# Boris_IO_5.net
KiCad netlist of a schematic drawn in Altium Designer
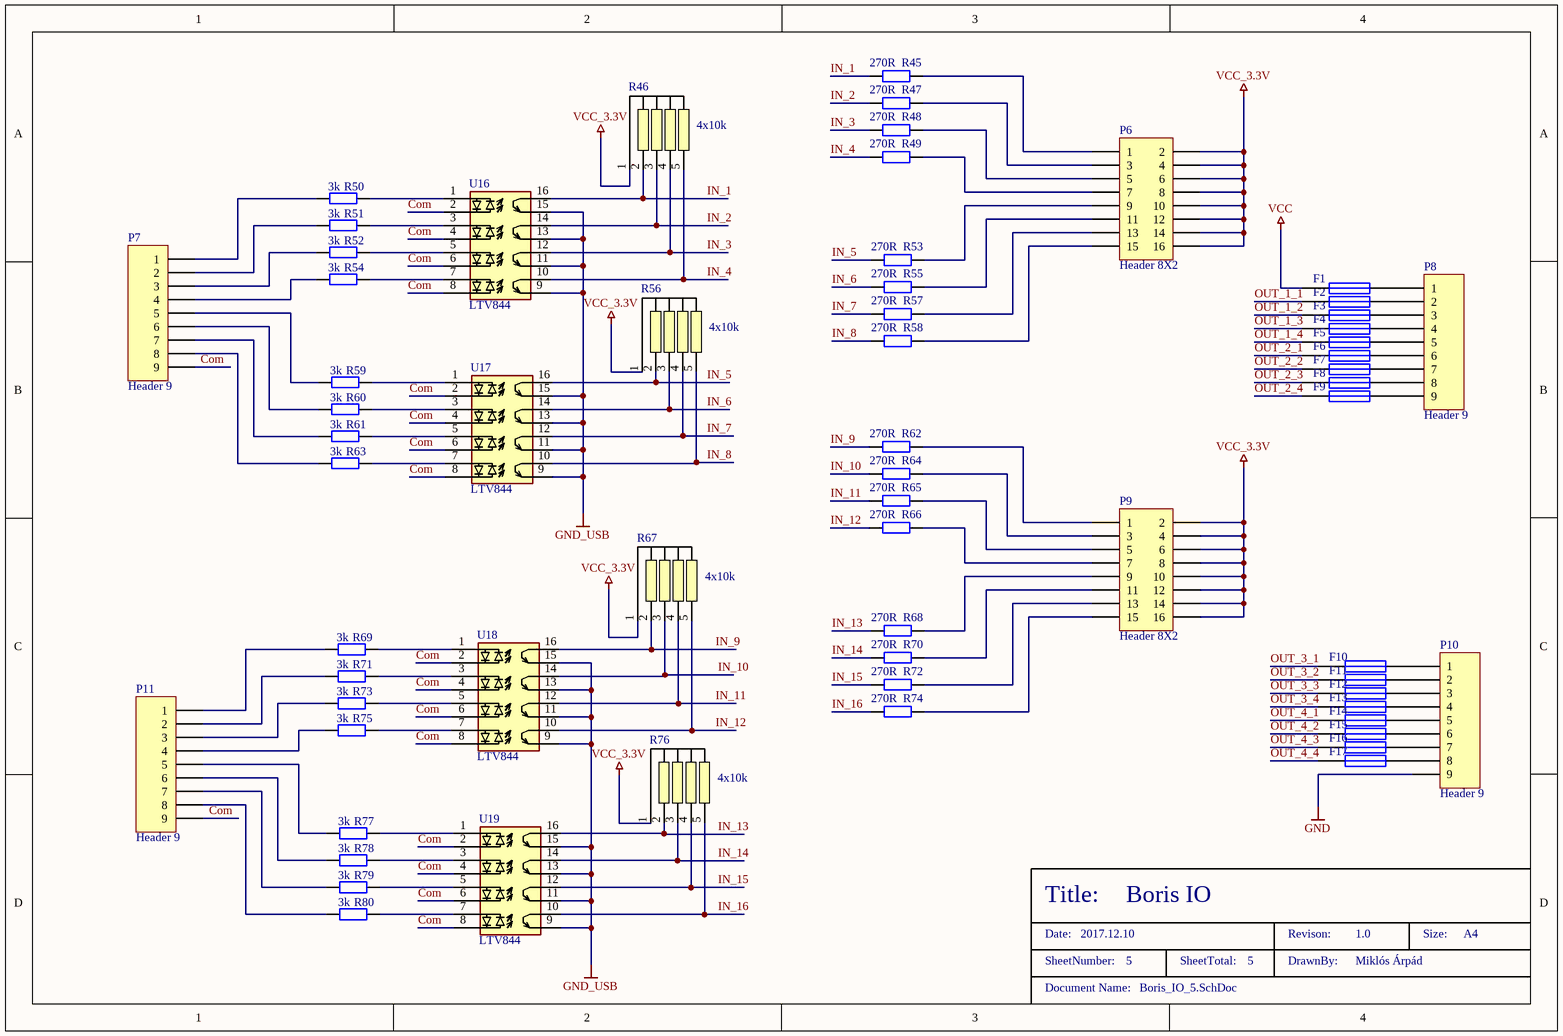
[diagram p0: Boris_IO_5.SchDoc]

(export (version "E")
  (design (tool "Eeschema 10.0.6"))
  (components
    (comp (ref "F1")
      (value "SSQ 0.25A")
      (footprint "SST6032")
      (description "Fuse")
      (fields (field (name "PUBLISHER") "Altium Limited"))
      (libsource (lib "IO-01") (part "Fuse 1"))
    )
    (comp (ref "F2")
      (value "SSQ 0.25A")
      (footprint "SST6032")
      (description "Fuse")
      (fields (field (name "PUBLISHER") "Altium Limited"))
      (libsource (lib "IO-01") (part "Fuse 1"))
    )
    (comp (ref "F3")
      (value "SSQ 0.25A")
      (footprint "SST6032")
      (description "Fuse")
      (fields (field (name "PUBLISHER") "Altium Limited"))
      (libsource (lib "IO-01") (part "Fuse 1"))
    )
    (comp (ref "F4")
      (value "SSQ 0.25A")
      (footprint "SST6032")
      (description "Fuse")
      (fields (field (name "PUBLISHER") "Altium Limited"))
      (libsource (lib "IO-01") (part "Fuse 1"))
    )
    (comp (ref "F5")
      (value "SSQ 0.25A")
      (footprint "SST6032")
      (description "Fuse")
      (fields (field (name "PUBLISHER") "Altium Limited"))
      (libsource (lib "IO-01") (part "Fuse 1"))
    )
    (comp (ref "F6")
      (value "SSQ 0.25A")
      (footprint "SST6032")
      (description "Fuse")
      (fields (field (name "PUBLISHER") "Altium Limited"))
      (libsource (lib "IO-01") (part "Fuse 1"))
    )
    (comp (ref "F7")
      (value "SSQ 0.25A")
      (footprint "SST6032")
      (description "Fuse")
      (fields (field (name "PUBLISHER") "Altium Limited"))
      (libsource (lib "IO-01") (part "Fuse 1"))
    )
    (comp (ref "F8")
      (value "SSQ 0.25A")
      (footprint "SST6032")
      (description "Fuse")
      (fields (field (name "PUBLISHER") "Altium Limited"))
      (libsource (lib "IO-01") (part "Fuse 1"))
    )
    (comp (ref "F9")
      (value "SSQ 0.25A")
      (footprint "SST6032")
      (description "Fuse")
      (fields (field (name "PUBLISHER") "Altium Limited"))
      (libsource (lib "IO-01") (part "Fuse 1"))
    )
    (comp (ref "F10")
      (value "SSQ 0.25A")
      (footprint "SST6032")
      (description "Fuse")
      (fields (field (name "PUBLISHER") "Altium Limited"))
      (libsource (lib "IO-01") (part "Fuse 1"))
    )
    (comp (ref "F11")
      (value "SSQ 0.25A")
      (footprint "SST6032")
      (description "Fuse")
      (fields (field (name "PUBLISHER") "Altium Limited"))
      (libsource (lib "IO-01") (part "Fuse 1"))
    )
    (comp (ref "F12")
      (value "SSQ 0.25A")
      (footprint "SST6032")
      (description "Fuse")
      (fields (field (name "PUBLISHER") "Altium Limited"))
      (libsource (lib "IO-01") (part "Fuse 1"))
    )
    (comp (ref "F13")
      (value "SSQ 0.25A")
      (footprint "SST6032")
      (description "Fuse")
      (fields (field (name "PUBLISHER") "Altium Limited"))
      (libsource (lib "IO-01") (part "Fuse 1"))
    )
    (comp (ref "F14")
      (value "SSQ 0.25A")
      (footprint "SST6032")
      (description "Fuse")
      (fields (field (name "PUBLISHER") "Altium Limited"))
      (libsource (lib "IO-01") (part "Fuse 1"))
    )
    (comp (ref "F15")
      (value "SSQ 0.25A")
      (footprint "SST6032")
      (description "Fuse")
      (fields (field (name "PUBLISHER") "Altium Limited"))
      (libsource (lib "IO-01") (part "Fuse 1"))
    )
    (comp (ref "F16")
      (value "SSQ 0.25A")
      (footprint "SST6032")
      (description "Fuse")
      (fields (field (name "PUBLISHER") "Altium Limited"))
      (libsource (lib "IO-01") (part "Fuse 1"))
    )
    (comp (ref "F17")
      (value "SSQ 0.25A")
      (footprint "SST6032")
      (description "Fuse")
      (fields (field (name "PUBLISHER") "Altium Limited"))
      (libsource (lib "IO-01") (part "Fuse 1"))
    )
    (comp (ref "P6")
      (value "Header 8X2")
      (footprint "HDR2X8")
      (description "Header, 8-Pin, Dual row")
      (fields (field (name "PUBLISHER") "Altium Limited"))
      (libsource (lib "Miscellaneous Connectors") (part "Header 8X2"))
    )
    (comp (ref "P7")
      (value "Header 9")
      (footprint "3x3")
      (description "Header, 9-Pin")
      (fields (field (name "PUBLISHER") "Altium Limited"))
      (libsource (lib "") (part "Header 9_1"))
    )
    (comp (ref "P8")
      (value "Header 9")
      (footprint "3x3")
      (description "Header, 9-Pin")
      (fields (field (name "PUBLISHER") "Altium Limited"))
      (libsource (lib "Miscellaneous Connectors") (part "Header 9"))
    )
    (comp (ref "P9")
      (value "Header 8X2")
      (footprint "HDR2X8")
      (description "Header, 8-Pin, Dual row")
      (fields (field (name "PUBLISHER") "Altium Limited"))
      (libsource (lib "Miscellaneous Connectors") (part "Header 8X2"))
    )
    (comp (ref "P10")
      (value "Header 9")
      (footprint "3x3")
      (description "Header, 9-Pin")
      (fields (field (name "PUBLISHER") "Altium Limited"))
      (libsource (lib "Miscellaneous Connectors") (part "Header 9"))
    )
    (comp (ref "P11")
      (value "Header 9")
      (footprint "3x3")
      (description "Header, 9-Pin")
      (fields (field (name "PUBLISHER") "Altium Limited"))
      (libsource (lib "") (part "Header 9_1"))
    )
    (comp (ref "R45")
      (value "270R")
      (footprint "0805_RES")
      (description "Resistor")
      (libsource (lib "Miscellaneous Devices") (part "Res2"))
    )
    (comp (ref "R46") (value "4x10k") (footprint "NFD_SIL-RES-5") (libsource (lib "IO-01") (part "SIL_10k")))
    (comp (ref "R47")
      (value "270R")
      (footprint "0805_RES")
      (description "Resistor")
      (libsource (lib "Miscellaneous Devices") (part "Res2"))
    )
    (comp (ref "R48")
      (value "270R")
      (footprint "0805_RES")
      (description "Resistor")
      (libsource (lib "Miscellaneous Devices") (part "Res2"))
    )
    (comp (ref "R49")
      (value "270R")
      (footprint "0805_RES")
      (description "Resistor")
      (libsource (lib "Miscellaneous Devices") (part "Res2"))
    )
    (comp (ref "R50")
      (value "3k")
      (footprint "RESC3216N")
      (description "Resistor")
      (libsource (lib "Miscellaneous Devices") (part "Res2"))
    )
    (comp (ref "R51")
      (value "3k")
      (footprint "RESC3216N")
      (description "Resistor")
      (libsource (lib "Miscellaneous Devices") (part "Res2"))
    )
    (comp (ref "R52")
      (value "3k")
      (footprint "RESC3216N")
      (description "Resistor")
      (libsource (lib "Miscellaneous Devices") (part "Res2"))
    )
    (comp (ref "R53")
      (value "270R")
      (footprint "0805_RES")
      (description "Resistor")
      (libsource (lib "Miscellaneous Devices") (part "Res2"))
    )
    (comp (ref "R54")
      (value "3k")
      (footprint "RESC3216N")
      (description "Resistor")
      (libsource (lib "Miscellaneous Devices") (part "Res2"))
    )
    (comp (ref "R55")
      (value "270R")
      (footprint "0805_RES")
      (description "Resistor")
      (libsource (lib "Miscellaneous Devices") (part "Res2"))
    )
    (comp (ref "R56") (value "4x10k") (footprint "NFD_SIL-RES-5") (libsource (lib "IO-01") (part "SIL_10k")))
    (comp (ref "R57")
      (value "270R")
      (footprint "0805_RES")
      (description "Resistor")
      (libsource (lib "Miscellaneous Devices") (part "Res2"))
    )
    (comp (ref "R58")
      (value "270R")
      (footprint "0805_RES")
      (description "Resistor")
      (libsource (lib "Miscellaneous Devices") (part "Res2"))
    )
    (comp (ref "R59")
      (value "3k")
      (footprint "RESC3216N")
      (description "Resistor")
      (libsource (lib "Miscellaneous Devices") (part "Res2"))
    )
    (comp (ref "R60")
      (value "3k")
      (footprint "RESC3216N")
      (description "Resistor")
      (libsource (lib "Miscellaneous Devices") (part "Res2"))
    )
    (comp (ref "R61")
      (value "3k")
      (footprint "RESC3216N")
      (description "Resistor")
      (libsource (lib "Miscellaneous Devices") (part "Res2"))
    )
    (comp (ref "R62")
      (value "270R")
      (footprint "0805_RES")
      (description "Resistor")
      (libsource (lib "Miscellaneous Devices") (part "Res2"))
    )
    (comp (ref "R63")
      (value "3k")
      (footprint "RESC3216N")
      (description "Resistor")
      (libsource (lib "Miscellaneous Devices") (part "Res2"))
    )
    (comp (ref "R64")
      (value "270R")
      (footprint "0805_RES")
      (description "Resistor")
      (libsource (lib "Miscellaneous Devices") (part "Res2"))
    )
    (comp (ref "R65")
      (value "270R")
      (footprint "0805_RES")
      (description "Resistor")
      (libsource (lib "Miscellaneous Devices") (part "Res2"))
    )
    (comp (ref "R66")
      (value "270R")
      (footprint "0805_RES")
      (description "Resistor")
      (libsource (lib "Miscellaneous Devices") (part "Res2"))
    )
    (comp (ref "R67") (value "4x10k") (footprint "NFD_SIL-RES-5") (libsource (lib "IO-01") (part "SIL_10k")))
    (comp (ref "R68")
      (value "270R")
      (footprint "0805_RES")
      (description "Resistor")
      (libsource (lib "Miscellaneous Devices") (part "Res2"))
    )
    (comp (ref "R69")
      (value "3k")
      (footprint "RESC3216N")
      (description "Resistor")
      (libsource (lib "Miscellaneous Devices") (part "Res2"))
    )
    (comp (ref "R70")
      (value "270R")
      (footprint "0805_RES")
      (description "Resistor")
      (libsource (lib "Miscellaneous Devices") (part "Res2"))
    )
    (comp (ref "R71")
      (value "3k")
      (footprint "RESC3216N")
      (description "Resistor")
      (libsource (lib "Miscellaneous Devices") (part "Res2"))
    )
    (comp (ref "R72")
      (value "270R")
      (footprint "0805_RES")
      (description "Resistor")
      (libsource (lib "Miscellaneous Devices") (part "Res2"))
    )
    (comp (ref "R73")
      (value "3k")
      (footprint "RESC3216N")
      (description "Resistor")
      (libsource (lib "Miscellaneous Devices") (part "Res2"))
    )
    (comp (ref "R74")
      (value "270R")
      (footprint "0805_RES")
      (description "Resistor")
      (libsource (lib "Miscellaneous Devices") (part "Res2"))
    )
    (comp (ref "R75")
      (value "3k")
      (footprint "RESC3216N")
      (description "Resistor")
      (libsource (lib "Miscellaneous Devices") (part "Res2"))
    )
    (comp (ref "R76") (value "4x10k") (footprint "NFD_SIL-RES-5") (libsource (lib "IO-01") (part "SIL_10k")))
    (comp (ref "R77")
      (value "3k")
      (footprint "RESC3216N")
      (description "Resistor")
      (libsource (lib "Miscellaneous Devices") (part "Res2"))
    )
    (comp (ref "R78")
      (value "3k")
      (footprint "RESC3216N")
      (description "Resistor")
      (libsource (lib "Miscellaneous Devices") (part "Res2"))
    )
    (comp (ref "R79")
      (value "3k")
      (footprint "RESC3216N")
      (description "Resistor")
      (libsource (lib "Miscellaneous Devices") (part "Res2"))
    )
    (comp (ref "R80")
      (value "3k")
      (footprint "RESC3216N")
      (description "Resistor")
      (libsource (lib "Miscellaneous Devices") (part "Res2"))
    )
    (comp (ref "U16")
      (value "LTV844")
      (footprint "LTV844S")
      (description "4x optocoupler")
      (libsource (lib "MisiIC1") (part "LTV844"))
    )
    (comp (ref "U17")
      (value "LTV844")
      (footprint "LTV844S")
      (description "4x optocoupler")
      (libsource (lib "MisiIC1") (part "LTV844"))
    )
    (comp (ref "U18")
      (value "LTV844")
      (footprint "LTV844S")
      (description "4x optocoupler")
      (libsource (lib "MisiIC1") (part "LTV844"))
    )
    (comp (ref "U19")
      (value "LTV844")
      (footprint "LTV844S")
      (description "4x optocoupler")
      (libsource (lib "MisiIC1") (part "LTV844"))
    )
  )
  (nets
    (net (code "1") (name "/Com") (class "Default")
      (node (ref "P11") (pin "9") (pinfunction "9_9") (pintype "passive"))
      (node (ref "P7") (pin "9") (pinfunction "9_9") (pintype "passive"))
      (node (ref "U16") (pin "2") (pinfunction "2_2") (pintype "passive"))
      (node (ref "U16") (pin "4") (pinfunction "4_4") (pintype "passive"))
      (node (ref "U16") (pin "6") (pinfunction "6_6") (pintype "passive"))
      (node (ref "U16") (pin "8") (pinfunction "8_8") (pintype "passive"))
      (node (ref "U17") (pin "2") (pinfunction "2_2") (pintype "passive"))
      (node (ref "U17") (pin "4") (pinfunction "4_4") (pintype "passive"))
      (node (ref "U17") (pin "6") (pinfunction "6_6") (pintype "passive"))
      (node (ref "U17") (pin "8") (pinfunction "8_8") (pintype "passive"))
      (node (ref "U18") (pin "2") (pinfunction "2_2") (pintype "passive"))
      (node (ref "U18") (pin "4") (pinfunction "4_4") (pintype "passive"))
      (node (ref "U18") (pin "6") (pinfunction "6_6") (pintype "passive"))
      (node (ref "U18") (pin "8") (pinfunction "8_8") (pintype "passive"))
      (node (ref "U19") (pin "2") (pinfunction "2_2") (pintype "passive"))
      (node (ref "U19") (pin "4") (pinfunction "4_4") (pintype "passive"))
      (node (ref "U19") (pin "6") (pinfunction "6_6") (pintype "passive"))
      (node (ref "U19") (pin "8") (pinfunction "8_8") (pintype "passive"))
    )
    (net (code "2") (name "/IN_1") (class "Default")
      (node (ref "R45") (pin "1") (pinfunction "1_1") (pintype "passive"))
      (node (ref "R46") (pin "2") (pinfunction "2_2") (pintype "passive"))
      (node (ref "U16") (pin "16") (pinfunction "16_16") (pintype "passive"))
    )
    (net (code "3") (name "/IN_2") (class "Default")
      (node (ref "R46") (pin "3") (pinfunction "3_3") (pintype "passive"))
      (node (ref "R47") (pin "1") (pinfunction "1_1") (pintype "passive"))
      (node (ref "U16") (pin "14") (pinfunction "14_14") (pintype "passive"))
    )
    (net (code "4") (name "/IN_3") (class "Default")
      (node (ref "R46") (pin "4") (pinfunction "4_4") (pintype "passive"))
      (node (ref "R48") (pin "1") (pinfunction "1_1") (pintype "passive"))
      (node (ref "U16") (pin "12") (pinfunction "12_12") (pintype "passive"))
    )
    (net (code "5") (name "/IN_4") (class "Default")
      (node (ref "R46") (pin "5") (pinfunction "5_5") (pintype "passive"))
      (node (ref "R49") (pin "1") (pinfunction "1_1") (pintype "passive"))
      (node (ref "U16") (pin "10") (pinfunction "10_10") (pintype "passive"))
    )
    (net (code "6") (name "/IN_5") (class "Default")
      (node (ref "R53") (pin "1") (pinfunction "1_1") (pintype "passive"))
      (node (ref "R56") (pin "2") (pinfunction "2_2") (pintype "passive"))
      (node (ref "U17") (pin "16") (pinfunction "16_16") (pintype "passive"))
    )
    (net (code "7") (name "/IN_6") (class "Default")
      (node (ref "R55") (pin "1") (pinfunction "1_1") (pintype "passive"))
      (node (ref "R56") (pin "3") (pinfunction "3_3") (pintype "passive"))
      (node (ref "U17") (pin "14") (pinfunction "14_14") (pintype "passive"))
    )
    (net (code "8") (name "/IN_7") (class "Default")
      (node (ref "R56") (pin "4") (pinfunction "4_4") (pintype "passive"))
      (node (ref "R57") (pin "1") (pinfunction "1_1") (pintype "passive"))
      (node (ref "U17") (pin "12") (pinfunction "12_12") (pintype "passive"))
    )
    (net (code "9") (name "/IN_8") (class "Default")
      (node (ref "R56") (pin "5") (pinfunction "5_5") (pintype "passive"))
      (node (ref "R58") (pin "1") (pinfunction "1_1") (pintype "passive"))
      (node (ref "U17") (pin "10") (pinfunction "10_10") (pintype "passive"))
    )
    (net (code "10") (name "/IN_9") (class "Default")
      (node (ref "R62") (pin "1") (pinfunction "1_1") (pintype "passive"))
      (node (ref "R67") (pin "2") (pinfunction "2_2") (pintype "passive"))
      (node (ref "U18") (pin "16") (pinfunction "16_16") (pintype "passive"))
    )
    (net (code "11") (name "/IN_10") (class "Default")
      (node (ref "R64") (pin "1") (pinfunction "1_1") (pintype "passive"))
      (node (ref "R67") (pin "3") (pinfunction "3_3") (pintype "passive"))
      (node (ref "U18") (pin "14") (pinfunction "14_14") (pintype "passive"))
    )
    (net (code "12") (name "/IN_11") (class "Default")
      (node (ref "R65") (pin "1") (pinfunction "1_1") (pintype "passive"))
      (node (ref "R67") (pin "4") (pinfunction "4_4") (pintype "passive"))
      (node (ref "U18") (pin "12") (pinfunction "12_12") (pintype "passive"))
    )
    (net (code "13") (name "/IN_12") (class "Default")
      (node (ref "R66") (pin "1") (pinfunction "1_1") (pintype "passive"))
      (node (ref "R67") (pin "5") (pinfunction "5_5") (pintype "passive"))
      (node (ref "U18") (pin "10") (pinfunction "10_10") (pintype "passive"))
    )
    (net (code "14") (name "/IN_13") (class "Default")
      (node (ref "R68") (pin "1") (pinfunction "1_1") (pintype "passive"))
      (node (ref "R76") (pin "2") (pinfunction "2_2") (pintype "passive"))
      (node (ref "U19") (pin "16") (pinfunction "16_16") (pintype "passive"))
    )
    (net (code "15") (name "/IN_14") (class "Default")
      (node (ref "R70") (pin "1") (pinfunction "1_1") (pintype "passive"))
      (node (ref "R76") (pin "3") (pinfunction "3_3") (pintype "passive"))
      (node (ref "U19") (pin "14") (pinfunction "14_14") (pintype "passive"))
    )
    (net (code "16") (name "/IN_15") (class "Default")
      (node (ref "R72") (pin "1") (pinfunction "1_1") (pintype "passive"))
      (node (ref "R76") (pin "4") (pinfunction "4_4") (pintype "passive"))
      (node (ref "U19") (pin "12") (pinfunction "12_12") (pintype "passive"))
    )
    (net (code "17") (name "/IN_16") (class "Default")
      (node (ref "R74") (pin "1") (pinfunction "1_1") (pintype "passive"))
      (node (ref "R76") (pin "5") (pinfunction "5_5") (pintype "passive"))
      (node (ref "U19") (pin "10") (pinfunction "10_10") (pintype "passive"))
    )
    (net (code "18") (name "/OUT_1_1") (class "Default")
      (node (ref "F2") (pin "1") (pinfunction "1_1") (pintype "passive"))
    )
    (net (code "19") (name "/OUT_1_2") (class "Default")
      (node (ref "F3") (pin "1") (pinfunction "1_1") (pintype "passive"))
    )
    (net (code "20") (name "/OUT_1_3") (class "Default")
      (node (ref "F4") (pin "1") (pinfunction "1_1") (pintype "passive"))
    )
    (net (code "21") (name "/OUT_1_4") (class "Default")
      (node (ref "F5") (pin "1") (pinfunction "1_1") (pintype "passive"))
    )
    (net (code "22") (name "/OUT_2_1") (class "Default")
      (node (ref "F6") (pin "1") (pinfunction "1_1") (pintype "passive"))
    )
    (net (code "23") (name "/OUT_2_2") (class "Default")
      (node (ref "F7") (pin "1") (pinfunction "1_1") (pintype "passive"))
    )
    (net (code "24") (name "/OUT_2_3") (class "Default")
      (node (ref "F8") (pin "1") (pinfunction "1_1") (pintype "passive"))
    )
    (net (code "25") (name "/OUT_2_4") (class "Default")
      (node (ref "F9") (pin "1") (pinfunction "1_1") (pintype "passive"))
    )
    (net (code "26") (name "/OUT_3_1") (class "Default")
      (node (ref "F10") (pin "1") (pinfunction "1_1") (pintype "passive"))
    )
    (net (code "27") (name "/OUT_3_2") (class "Default")
      (node (ref "F11") (pin "1") (pinfunction "1_1") (pintype "passive"))
    )
    (net (code "28") (name "/OUT_3_3") (class "Default")
      (node (ref "F12") (pin "1") (pinfunction "1_1") (pintype "passive"))
    )
    (net (code "29") (name "/OUT_3_4") (class "Default")
      (node (ref "F13") (pin "1") (pinfunction "1_1") (pintype "passive"))
    )
    (net (code "30") (name "/OUT_4_1") (class "Default")
      (node (ref "F14") (pin "1") (pinfunction "1_1") (pintype "passive"))
    )
    (net (code "31") (name "/OUT_4_2") (class "Default")
      (node (ref "F15") (pin "1") (pinfunction "1_1") (pintype "passive"))
    )
    (net (code "32") (name "/OUT_4_3") (class "Default")
      (node (ref "F16") (pin "1") (pinfunction "1_1") (pintype "passive"))
    )
    (net (code "33") (name "/OUT_4_4") (class "Default")
      (node (ref "F17") (pin "1") (pinfunction "1_1") (pintype "passive"))
    )
    (net (code "34") (name "GND") (class "Default")
      (node (ref "P10") (pin "9") (pinfunction "9_9") (pintype "passive"))
    )
    (net (code "35") (name "GND_USB") (class "Default")
      (node (ref "U16") (pin "11") (pinfunction "11_11") (pintype "passive"))
      (node (ref "U16") (pin "13") (pinfunction "13_13") (pintype "passive"))
      (node (ref "U16") (pin "15") (pinfunction "15_15") (pintype "passive"))
      (node (ref "U16") (pin "9") (pinfunction "9_9") (pintype "passive"))
      (node (ref "U17") (pin "11") (pinfunction "11_11") (pintype "passive"))
      (node (ref "U17") (pin "13") (pinfunction "13_13") (pintype "passive"))
      (node (ref "U17") (pin "15") (pinfunction "15_15") (pintype "passive"))
      (node (ref "U17") (pin "9") (pinfunction "9_9") (pintype "passive"))
      (node (ref "U18") (pin "11") (pinfunction "11_11") (pintype "passive"))
      (node (ref "U18") (pin "13") (pinfunction "13_13") (pintype "passive"))
      (node (ref "U18") (pin "15") (pinfunction "15_15") (pintype "passive"))
      (node (ref "U18") (pin "9") (pinfunction "9_9") (pintype "passive"))
      (node (ref "U19") (pin "11") (pinfunction "11_11") (pintype "passive"))
      (node (ref "U19") (pin "13") (pinfunction "13_13") (pintype "passive"))
      (node (ref "U19") (pin "15") (pinfunction "15_15") (pintype "passive"))
      (node (ref "U19") (pin "9") (pinfunction "9_9") (pintype "passive"))
    )
    (net (code "36") (name "Net-(F1-Pad2)") (class "Default")
      (node (ref "F1") (pin "2") (pinfunction "2_2") (pintype "passive"))
      (node (ref "P8") (pin "1") (pinfunction "1_1") (pintype "passive"))
    )
    (net (code "37") (name "Net-(F2-Pad2)") (class "Default")
      (node (ref "F2") (pin "2") (pinfunction "2_2") (pintype "passive"))
      (node (ref "P8") (pin "2") (pinfunction "2_2") (pintype "passive"))
    )
    (net (code "38") (name "Net-(F3-Pad2)") (class "Default")
      (node (ref "F3") (pin "2") (pinfunction "2_2") (pintype "passive"))
      (node (ref "P8") (pin "3") (pinfunction "3_3") (pintype "passive"))
    )
    (net (code "39") (name "Net-(F4-Pad2)") (class "Default")
      (node (ref "F4") (pin "2") (pinfunction "2_2") (pintype "passive"))
      (node (ref "P8") (pin "4") (pinfunction "4_4") (pintype "passive"))
    )
    (net (code "40") (name "Net-(F5-Pad2)") (class "Default")
      (node (ref "F5") (pin "2") (pinfunction "2_2") (pintype "passive"))
      (node (ref "P8") (pin "5") (pinfunction "5_5") (pintype "passive"))
    )
    (net (code "41") (name "Net-(F6-Pad2)") (class "Default")
      (node (ref "F6") (pin "2") (pinfunction "2_2") (pintype "passive"))
      (node (ref "P8") (pin "6") (pinfunction "6_6") (pintype "passive"))
    )
    (net (code "42") (name "Net-(F7-Pad2)") (class "Default")
      (node (ref "F7") (pin "2") (pinfunction "2_2") (pintype "passive"))
      (node (ref "P8") (pin "7") (pinfunction "7_7") (pintype "passive"))
    )
    (net (code "43") (name "Net-(F8-Pad2)") (class "Default")
      (node (ref "F8") (pin "2") (pinfunction "2_2") (pintype "passive"))
      (node (ref "P8") (pin "8") (pinfunction "8_8") (pintype "passive"))
    )
    (net (code "44") (name "Net-(F9-Pad2)") (class "Default")
      (node (ref "F9") (pin "2") (pinfunction "2_2") (pintype "passive"))
      (node (ref "P8") (pin "9") (pinfunction "9_9") (pintype "passive"))
    )
    (net (code "45") (name "Net-(F10-Pad2)") (class "Default")
      (node (ref "F10") (pin "2") (pinfunction "2_2") (pintype "passive"))
      (node (ref "P10") (pin "1") (pinfunction "1_1") (pintype "passive"))
    )
    (net (code "46") (name "Net-(F11-Pad2)") (class "Default")
      (node (ref "F11") (pin "2") (pinfunction "2_2") (pintype "passive"))
      (node (ref "P10") (pin "2") (pinfunction "2_2") (pintype "passive"))
    )
    (net (code "47") (name "Net-(F12-Pad2)") (class "Default")
      (node (ref "F12") (pin "2") (pinfunction "2_2") (pintype "passive"))
      (node (ref "P10") (pin "3") (pinfunction "3_3") (pintype "passive"))
    )
    (net (code "48") (name "Net-(F13-Pad2)") (class "Default")
      (node (ref "F13") (pin "2") (pinfunction "2_2") (pintype "passive"))
      (node (ref "P10") (pin "4") (pinfunction "4_4") (pintype "passive"))
    )
    (net (code "49") (name "Net-(F14-Pad2)") (class "Default")
      (node (ref "F14") (pin "2") (pinfunction "2_2") (pintype "passive"))
      (node (ref "P10") (pin "5") (pinfunction "5_5") (pintype "passive"))
    )
    (net (code "50") (name "Net-(F15-Pad2)") (class "Default")
      (node (ref "F15") (pin "2") (pinfunction "2_2") (pintype "passive"))
      (node (ref "P10") (pin "6") (pinfunction "6_6") (pintype "passive"))
    )
    (net (code "51") (name "Net-(F16-Pad2)") (class "Default")
      (node (ref "F16") (pin "2") (pinfunction "2_2") (pintype "passive"))
      (node (ref "P10") (pin "7") (pinfunction "7_7") (pintype "passive"))
    )
    (net (code "52") (name "Net-(F17-Pad2)") (class "Default")
      (node (ref "F17") (pin "2") (pinfunction "2_2") (pintype "passive"))
      (node (ref "P10") (pin "8") (pinfunction "8_8") (pintype "passive"))
    )
    (net (code "53") (name "Net-(P6-Pad1)") (class "Default")
      (node (ref "P6") (pin "1") (pinfunction "1_1") (pintype "passive"))
      (node (ref "R45") (pin "2") (pinfunction "2_2") (pintype "passive"))
    )
    (net (code "54") (name "Net-(P6-Pad3)") (class "Default")
      (node (ref "P6") (pin "3") (pinfunction "3_3") (pintype "passive"))
      (node (ref "R47") (pin "2") (pinfunction "2_2") (pintype "passive"))
    )
    (net (code "55") (name "Net-(P6-Pad5)") (class "Default")
      (node (ref "P6") (pin "5") (pinfunction "5_5") (pintype "passive"))
      (node (ref "R48") (pin "2") (pinfunction "2_2") (pintype "passive"))
    )
    (net (code "56") (name "Net-(P6-Pad7)") (class "Default")
      (node (ref "P6") (pin "7") (pinfunction "7_7") (pintype "passive"))
      (node (ref "R49") (pin "2") (pinfunction "2_2") (pintype "passive"))
    )
    (net (code "57") (name "Net-(P6-Pad9)") (class "Default")
      (node (ref "P6") (pin "9") (pinfunction "9_9") (pintype "passive"))
      (node (ref "R53") (pin "2") (pinfunction "2_2") (pintype "passive"))
    )
    (net (code "58") (name "Net-(P6-Pad11)") (class "Default")
      (node (ref "P6") (pin "11") (pinfunction "11_11") (pintype "passive"))
      (node (ref "R55") (pin "2") (pinfunction "2_2") (pintype "passive"))
    )
    (net (code "59") (name "Net-(P6-Pad13)") (class "Default")
      (node (ref "P6") (pin "13") (pinfunction "13_13") (pintype "passive"))
      (node (ref "R57") (pin "2") (pinfunction "2_2") (pintype "passive"))
    )
    (net (code "60") (name "Net-(P6-Pad15)") (class "Default")
      (node (ref "P6") (pin "15") (pinfunction "15_15") (pintype "passive"))
      (node (ref "R58") (pin "2") (pinfunction "2_2") (pintype "passive"))
    )
    (net (code "61") (name "Net-(P7-Pad1)") (class "Default")
      (node (ref "P7") (pin "1") (pinfunction "1_1") (pintype "passive"))
      (node (ref "R50") (pin "1") (pinfunction "1_1") (pintype "passive"))
    )
    (net (code "62") (name "Net-(P7-Pad2)") (class "Default")
      (node (ref "P7") (pin "2") (pinfunction "2_2") (pintype "passive"))
      (node (ref "R51") (pin "1") (pinfunction "1_1") (pintype "passive"))
    )
    (net (code "63") (name "Net-(P7-Pad3)") (class "Default")
      (node (ref "P7") (pin "3") (pinfunction "3_3") (pintype "passive"))
      (node (ref "R52") (pin "1") (pinfunction "1_1") (pintype "passive"))
    )
    (net (code "64") (name "Net-(P7-Pad4)") (class "Default")
      (node (ref "P7") (pin "4") (pinfunction "4_4") (pintype "passive"))
      (node (ref "R54") (pin "1") (pinfunction "1_1") (pintype "passive"))
    )
    (net (code "65") (name "Net-(P7-Pad5)") (class "Default")
      (node (ref "P7") (pin "5") (pinfunction "5_5") (pintype "passive"))
      (node (ref "R59") (pin "1") (pinfunction "1_1") (pintype "passive"))
    )
    (net (code "66") (name "Net-(P7-Pad6)") (class "Default")
      (node (ref "P7") (pin "6") (pinfunction "6_6") (pintype "passive"))
      (node (ref "R60") (pin "1") (pinfunction "1_1") (pintype "passive"))
    )
    (net (code "67") (name "Net-(P7-Pad7)") (class "Default")
      (node (ref "P7") (pin "7") (pinfunction "7_7") (pintype "passive"))
      (node (ref "R61") (pin "1") (pinfunction "1_1") (pintype "passive"))
    )
    (net (code "68") (name "Net-(P7-Pad8)") (class "Default")
      (node (ref "P7") (pin "8") (pinfunction "8_8") (pintype "passive"))
      (node (ref "R63") (pin "1") (pinfunction "1_1") (pintype "passive"))
    )
    (net (code "69") (name "Net-(P9-Pad1)") (class "Default")
      (node (ref "P9") (pin "1") (pinfunction "1_1") (pintype "passive"))
      (node (ref "R62") (pin "2") (pinfunction "2_2") (pintype "passive"))
    )
    (net (code "70") (name "Net-(P9-Pad3)") (class "Default")
      (node (ref "P9") (pin "3") (pinfunction "3_3") (pintype "passive"))
      (node (ref "R64") (pin "2") (pinfunction "2_2") (pintype "passive"))
    )
    (net (code "71") (name "Net-(P9-Pad5)") (class "Default")
      (node (ref "P9") (pin "5") (pinfunction "5_5") (pintype "passive"))
      (node (ref "R65") (pin "2") (pinfunction "2_2") (pintype "passive"))
    )
    (net (code "72") (name "Net-(P9-Pad7)") (class "Default")
      (node (ref "P9") (pin "7") (pinfunction "7_7") (pintype "passive"))
      (node (ref "R66") (pin "2") (pinfunction "2_2") (pintype "passive"))
    )
    (net (code "73") (name "Net-(P9-Pad9)") (class "Default")
      (node (ref "P9") (pin "9") (pinfunction "9_9") (pintype "passive"))
      (node (ref "R68") (pin "2") (pinfunction "2_2") (pintype "passive"))
    )
    (net (code "74") (name "Net-(P9-Pad11)") (class "Default")
      (node (ref "P9") (pin "11") (pinfunction "11_11") (pintype "passive"))
      (node (ref "R70") (pin "2") (pinfunction "2_2") (pintype "passive"))
    )
    (net (code "75") (name "Net-(P9-Pad13)") (class "Default")
      (node (ref "P9") (pin "13") (pinfunction "13_13") (pintype "passive"))
      (node (ref "R72") (pin "2") (pinfunction "2_2") (pintype "passive"))
    )
    (net (code "76") (name "Net-(P9-Pad15)") (class "Default")
      (node (ref "P9") (pin "15") (pinfunction "15_15") (pintype "passive"))
      (node (ref "R74") (pin "2") (pinfunction "2_2") (pintype "passive"))
    )
    (net (code "77") (name "Net-(P11-Pad1)") (class "Default")
      (node (ref "P11") (pin "1") (pinfunction "1_1") (pintype "passive"))
      (node (ref "R69") (pin "1") (pinfunction "1_1") (pintype "passive"))
    )
    (net (code "78") (name "Net-(P11-Pad2)") (class "Default")
      (node (ref "P11") (pin "2") (pinfunction "2_2") (pintype "passive"))
      (node (ref "R71") (pin "1") (pinfunction "1_1") (pintype "passive"))
    )
    (net (code "79") (name "Net-(P11-Pad3)") (class "Default")
      (node (ref "P11") (pin "3") (pinfunction "3_3") (pintype "passive"))
      (node (ref "R73") (pin "1") (pinfunction "1_1") (pintype "passive"))
    )
    (net (code "80") (name "Net-(P11-Pad4)") (class "Default")
      (node (ref "P11") (pin "4") (pinfunction "4_4") (pintype "passive"))
      (node (ref "R75") (pin "1") (pinfunction "1_1") (pintype "passive"))
    )
    (net (code "81") (name "Net-(P11-Pad5)") (class "Default")
      (node (ref "P11") (pin "5") (pinfunction "5_5") (pintype "passive"))
      (node (ref "R77") (pin "1") (pinfunction "1_1") (pintype "passive"))
    )
    (net (code "82") (name "Net-(P11-Pad6)") (class "Default")
      (node (ref "P11") (pin "6") (pinfunction "6_6") (pintype "passive"))
      (node (ref "R78") (pin "1") (pinfunction "1_1") (pintype "passive"))
    )
    (net (code "83") (name "Net-(P11-Pad7)") (class "Default")
      (node (ref "P11") (pin "7") (pinfunction "7_7") (pintype "passive"))
      (node (ref "R79") (pin "1") (pinfunction "1_1") (pintype "passive"))
    )
    (net (code "84") (name "Net-(P11-Pad8)") (class "Default")
      (node (ref "P11") (pin "8") (pinfunction "8_8") (pintype "passive"))
      (node (ref "R80") (pin "1") (pinfunction "1_1") (pintype "passive"))
    )
    (net (code "85") (name "Net-(R50-Pad2)") (class "Default")
      (node (ref "R50") (pin "2") (pinfunction "2_2") (pintype "passive"))
      (node (ref "U16") (pin "1") (pinfunction "1_1") (pintype "passive"))
    )
    (net (code "86") (name "Net-(R51-Pad2)") (class "Default")
      (node (ref "R51") (pin "2") (pinfunction "2_2") (pintype "passive"))
      (node (ref "U16") (pin "3") (pinfunction "3_3") (pintype "passive"))
    )
    (net (code "87") (name "Net-(R52-Pad2)") (class "Default")
      (node (ref "R52") (pin "2") (pinfunction "2_2") (pintype "passive"))
      (node (ref "U16") (pin "5") (pinfunction "5_5") (pintype "passive"))
    )
    (net (code "88") (name "Net-(R54-Pad2)") (class "Default")
      (node (ref "R54") (pin "2") (pinfunction "2_2") (pintype "passive"))
      (node (ref "U16") (pin "7") (pinfunction "7_7") (pintype "passive"))
    )
    (net (code "89") (name "Net-(R59-Pad2)") (class "Default")
      (node (ref "R59") (pin "2") (pinfunction "2_2") (pintype "passive"))
      (node (ref "U17") (pin "1") (pinfunction "1_1") (pintype "passive"))
    )
    (net (code "90") (name "Net-(R60-Pad2)") (class "Default")
      (node (ref "R60") (pin "2") (pinfunction "2_2") (pintype "passive"))
      (node (ref "U17") (pin "3") (pinfunction "3_3") (pintype "passive"))
    )
    (net (code "91") (name "Net-(R61-Pad2)") (class "Default")
      (node (ref "R61") (pin "2") (pinfunction "2_2") (pintype "passive"))
      (node (ref "U17") (pin "5") (pinfunction "5_5") (pintype "passive"))
    )
    (net (code "92") (name "Net-(R63-Pad2)") (class "Default")
      (node (ref "R63") (pin "2") (pinfunction "2_2") (pintype "passive"))
      (node (ref "U17") (pin "7") (pinfunction "7_7") (pintype "passive"))
    )
    (net (code "93") (name "Net-(R69-Pad2)") (class "Default")
      (node (ref "R69") (pin "2") (pinfunction "2_2") (pintype "passive"))
      (node (ref "U18") (pin "1") (pinfunction "1_1") (pintype "passive"))
    )
    (net (code "94") (name "Net-(R71-Pad2)") (class "Default")
      (node (ref "R71") (pin "2") (pinfunction "2_2") (pintype "passive"))
      (node (ref "U18") (pin "3") (pinfunction "3_3") (pintype "passive"))
    )
    (net (code "95") (name "Net-(R73-Pad2)") (class "Default")
      (node (ref "R73") (pin "2") (pinfunction "2_2") (pintype "passive"))
      (node (ref "U18") (pin "5") (pinfunction "5_5") (pintype "passive"))
    )
    (net (code "96") (name "Net-(R75-Pad2)") (class "Default")
      (node (ref "R75") (pin "2") (pinfunction "2_2") (pintype "passive"))
      (node (ref "U18") (pin "7") (pinfunction "7_7") (pintype "passive"))
    )
    (net (code "97") (name "Net-(R77-Pad2)") (class "Default")
      (node (ref "R77") (pin "2") (pinfunction "2_2") (pintype "passive"))
      (node (ref "U19") (pin "1") (pinfunction "1_1") (pintype "passive"))
    )
    (net (code "98") (name "Net-(R78-Pad2)") (class "Default")
      (node (ref "R78") (pin "2") (pinfunction "2_2") (pintype "passive"))
      (node (ref "U19") (pin "3") (pinfunction "3_3") (pintype "passive"))
    )
    (net (code "99") (name "Net-(R79-Pad2)") (class "Default")
      (node (ref "R79") (pin "2") (pinfunction "2_2") (pintype "passive"))
      (node (ref "U19") (pin "5") (pinfunction "5_5") (pintype "passive"))
    )
    (net (code "100") (name "Net-(R80-Pad2)") (class "Default")
      (node (ref "R80") (pin "2") (pinfunction "2_2") (pintype "passive"))
      (node (ref "U19") (pin "7") (pinfunction "7_7") (pintype "passive"))
    )
    (net (code "101") (name "VCC") (class "Default")
      (node (ref "F1") (pin "1") (pinfunction "1_1") (pintype "passive"))
    )
    (net (code "102") (name "VCC_3.3V") (class "Default")
      (node (ref "P6") (pin "10") (pinfunction "10_10") (pintype "passive"))
      (node (ref "P6") (pin "12") (pinfunction "12_12") (pintype "passive"))
      (node (ref "P6") (pin "14") (pinfunction "14_14") (pintype "passive"))
      (node (ref "P6") (pin "16") (pinfunction "16_16") (pintype "passive"))
      (node (ref "P6") (pin "2") (pinfunction "2_2") (pintype "passive"))
      (node (ref "P6") (pin "4") (pinfunction "4_4") (pintype "passive"))
      (node (ref "P6") (pin "6") (pinfunction "6_6") (pintype "passive"))
      (node (ref "P6") (pin "8") (pinfunction "8_8") (pintype "passive"))
      (node (ref "P9") (pin "10") (pinfunction "10_10") (pintype "passive"))
      (node (ref "P9") (pin "12") (pinfunction "12_12") (pintype "passive"))
      (node (ref "P9") (pin "14") (pinfunction "14_14") (pintype "passive"))
      (node (ref "P9") (pin "16") (pinfunction "16_16") (pintype "passive"))
      (node (ref "P9") (pin "2") (pinfunction "2_2") (pintype "passive"))
      (node (ref "P9") (pin "4") (pinfunction "4_4") (pintype "passive"))
      (node (ref "P9") (pin "6") (pinfunction "6_6") (pintype "passive"))
      (node (ref "P9") (pin "8") (pinfunction "8_8") (pintype "passive"))
      (node (ref "R46") (pin "1") (pinfunction "1_1") (pintype "passive"))
      (node (ref "R56") (pin "1") (pinfunction "1_1") (pintype "passive"))
      (node (ref "R67") (pin "1") (pinfunction "1_1") (pintype "passive"))
      (node (ref "R76") (pin "1") (pinfunction "1_1") (pintype "passive"))
    )
  )
)
